# TouchPanel_ver__5.net
KiCad netlist of a schematic drawn in EAGLE
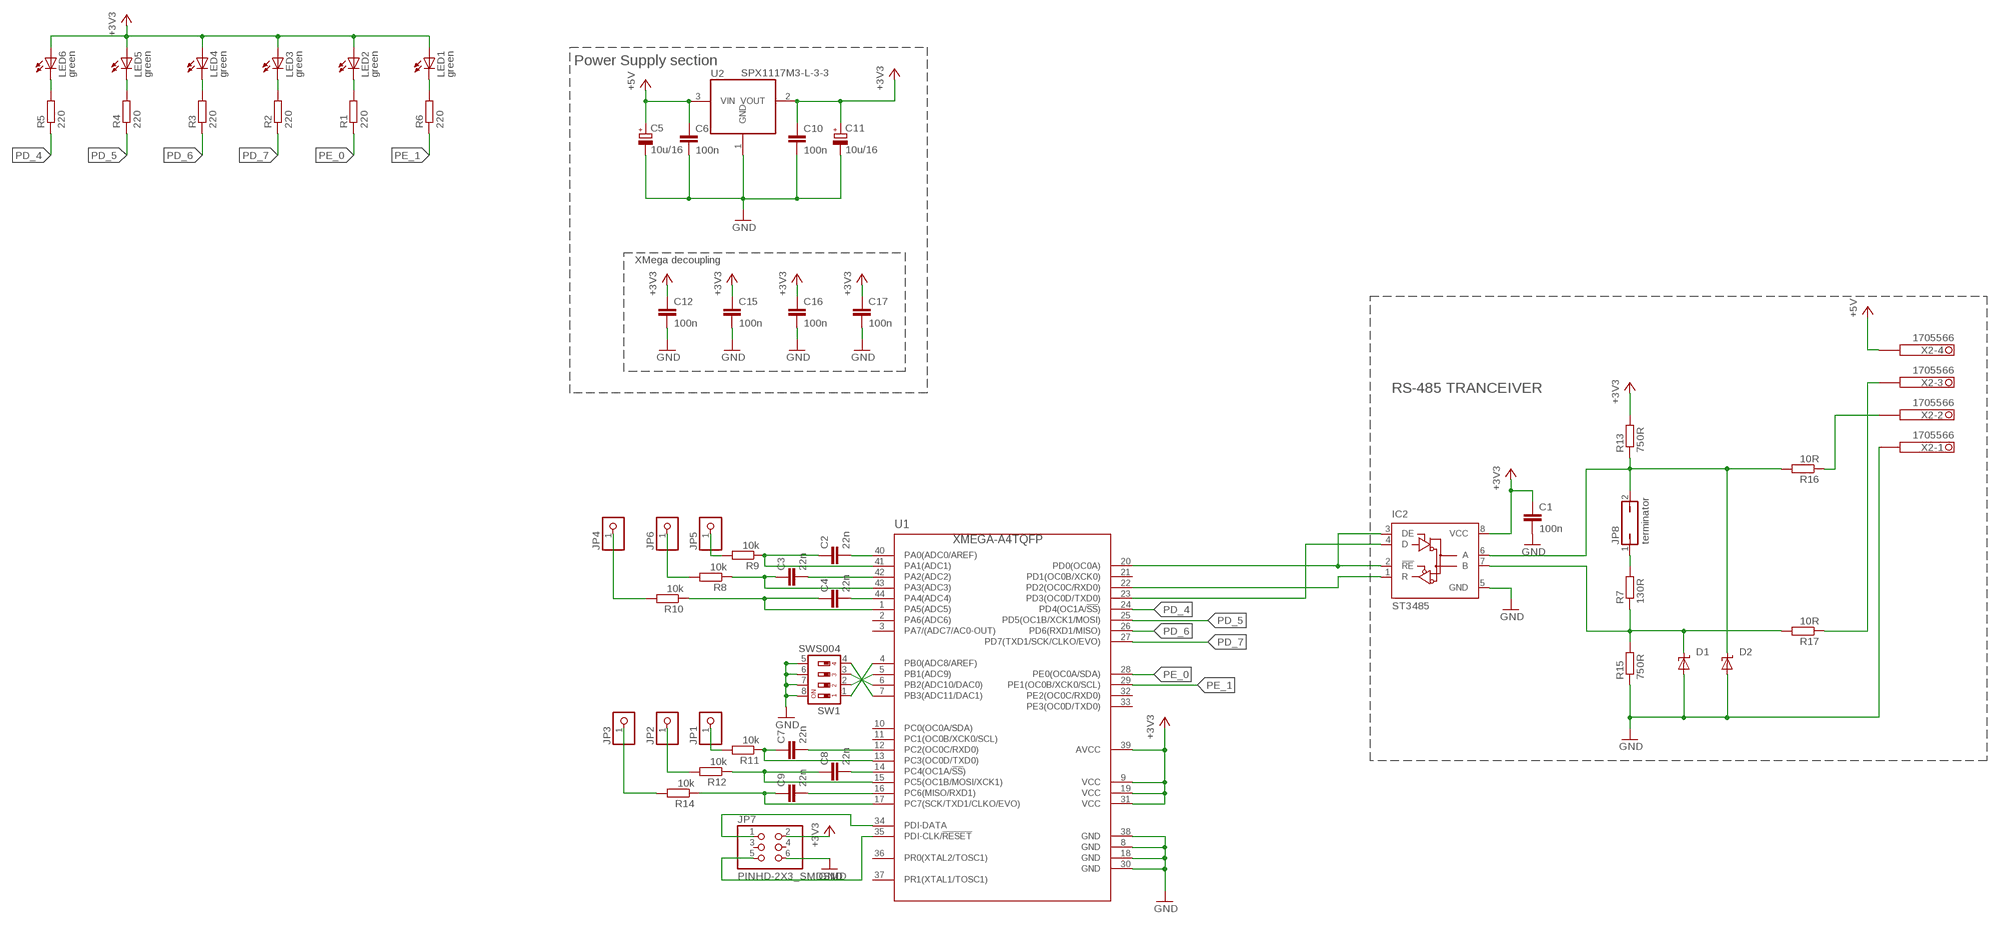
[diagram p0: schematic, sheet 1]

(export (version "E")
  (design (tool "Eeschema 10.0.6"))
  (components
    (comp (ref "C1")
      (value "100n")
      (footprint "eagle-import:C1206")
      (libsource (lib "eagle-import") (part "C-EUC1206"))
    )
    (comp (ref "C2")
      (value "22n")
      (footprint "eagle-import:C1206")
      (libsource (lib "eagle-import") (part "C-EUC1206"))
    )
    (comp (ref "C3")
      (value "22n")
      (footprint "eagle-import:C1206")
      (libsource (lib "eagle-import") (part "C-EUC1206"))
    )
    (comp (ref "C4")
      (value "22n")
      (footprint "eagle-import:C1206")
      (libsource (lib "eagle-import") (part "C-EUC1206"))
    )
    (comp (ref "C5")
      (value "10u/16")
      (footprint "eagle-import:SMC_B")
      (libsource (lib "eagle-import") (part "CPOL-EUSMCB"))
    )
    (comp (ref "C6")
      (value "100n")
      (footprint "eagle-import:C1206")
      (libsource (lib "eagle-import") (part "C-EUC1206"))
    )
    (comp (ref "C7")
      (value "22n")
      (footprint "eagle-import:C1206")
      (libsource (lib "eagle-import") (part "C-EUC1206"))
    )
    (comp (ref "C8")
      (value "22n")
      (footprint "eagle-import:C1206")
      (libsource (lib "eagle-import") (part "C-EUC1206"))
    )
    (comp (ref "C9")
      (value "22n")
      (footprint "eagle-import:C1206")
      (libsource (lib "eagle-import") (part "C-EUC1206"))
    )
    (comp (ref "C10")
      (value "100n")
      (footprint "eagle-import:C1206")
      (libsource (lib "eagle-import") (part "C-EUC1206"))
    )
    (comp (ref "C11")
      (value "10u/16")
      (footprint "eagle-import:SMC_B")
      (libsource (lib "eagle-import") (part "CPOL-EUSMCB"))
    )
    (comp (ref "C12")
      (value "100n")
      (footprint "eagle-import:C1206")
      (libsource (lib "eagle-import") (part "C-EUC1206"))
    )
    (comp (ref "C15")
      (value "100n")
      (footprint "eagle-import:C1206")
      (libsource (lib "eagle-import") (part "C-EUC1206"))
    )
    (comp (ref "C16")
      (value "100n")
      (footprint "eagle-import:C1206")
      (libsource (lib "eagle-import") (part "C-EUC1206"))
    )
    (comp (ref "C17")
      (value "100n")
      (footprint "eagle-import:C1206")
      (libsource (lib "eagle-import") (part "C-EUC1206"))
    )
    (comp (ref "D1")
      (value "SUPPRESSOR-SMBJ")
      (footprint "eagle-import:SMBJ")
      (libsource (lib "eagle-import") (part "SUPPRESSOR-SMBJ"))
    )
    (comp (ref "D2")
      (value "SUPPRESSOR-SMBJ")
      (footprint "eagle-import:SMBJ")
      (libsource (lib "eagle-import") (part "SUPPRESSOR-SMBJ"))
    )
    (comp (ref "IC2")
      (value "ST3485")
      (footprint "eagle-import:D_R-PDSO-G8")
      (libsource (lib "eagle-import") (part "75176AD"))
    )
    (comp (ref "JP1")
      (value "PINHD-1X1")
      (footprint "eagle-import:1X01")
      (libsource (lib "eagle-import") (part "PINHD-1X1"))
    )
    (comp (ref "JP2")
      (value "PINHD-1X1")
      (footprint "eagle-import:1X01")
      (libsource (lib "eagle-import") (part "PINHD-1X1"))
    )
    (comp (ref "JP3")
      (value "PINHD-1X1")
      (footprint "eagle-import:1X01")
      (libsource (lib "eagle-import") (part "PINHD-1X1"))
    )
    (comp (ref "JP4")
      (value "PINHD-1X1")
      (footprint "eagle-import:1X01")
      (libsource (lib "eagle-import") (part "PINHD-1X1"))
    )
    (comp (ref "JP5")
      (value "PINHD-1X1")
      (footprint "eagle-import:1X01")
      (libsource (lib "eagle-import") (part "PINHD-1X1"))
    )
    (comp (ref "JP6")
      (value "PINHD-1X1")
      (footprint "eagle-import:1X01")
      (libsource (lib "eagle-import") (part "PINHD-1X1"))
    )
    (comp (ref "JP7")
      (value "PINHD-2X3_SMDSMD")
      (footprint "eagle-import:2X03_SMD")
      (libsource (lib "eagle-import") (part "PINHD-2X3_SMDSMD"))
    )
    (comp (ref "JP8")
      (value "terminator")
      (footprint "eagle-import:JP1")
      (libsource (lib "eagle-import") (part "JP1Q"))
    )
    (comp (ref "LED1")
      (value "green")
      (footprint "eagle-import:MINI-TOPLED-SANTANA")
      (libsource (lib "eagle-import") (part "LEDTOPLED-SANTANA"))
    )
    (comp (ref "LED2")
      (value "green")
      (footprint "eagle-import:MINI-TOPLED-SANTANA")
      (libsource (lib "eagle-import") (part "LEDTOPLED-SANTANA"))
    )
    (comp (ref "LED3")
      (value "green")
      (footprint "eagle-import:MINI-TOPLED-SANTANA")
      (libsource (lib "eagle-import") (part "LEDTOPLED-SANTANA"))
    )
    (comp (ref "LED4")
      (value "green")
      (footprint "eagle-import:MINI-TOPLED-SANTANA")
      (libsource (lib "eagle-import") (part "LEDTOPLED-SANTANA"))
    )
    (comp (ref "LED5")
      (value "green")
      (footprint "eagle-import:MINI-TOPLED-SANTANA")
      (libsource (lib "eagle-import") (part "LEDTOPLED-SANTANA"))
    )
    (comp (ref "LED6")
      (value "green")
      (footprint "eagle-import:MINI-TOPLED-SANTANA")
      (libsource (lib "eagle-import") (part "LEDTOPLED-SANTANA"))
    )
    (comp (ref "R1")
      (value "220")
      (footprint "eagle-import:M1206")
      (libsource (lib "eagle-import") (part "R-EU_M1206"))
    )
    (comp (ref "R2")
      (value "220")
      (footprint "eagle-import:M1206")
      (libsource (lib "eagle-import") (part "R-EU_M1206"))
    )
    (comp (ref "R3")
      (value "220")
      (footprint "eagle-import:R1206")
      (libsource (lib "eagle-import") (part "R-EU_R1206"))
    )
    (comp (ref "R4")
      (value "220")
      (footprint "eagle-import:R1206")
      (libsource (lib "eagle-import") (part "R-EU_R1206"))
    )
    (comp (ref "R5")
      (value "220")
      (footprint "eagle-import:R1206")
      (libsource (lib "eagle-import") (part "R-EU_R1206"))
    )
    (comp (ref "R6")
      (value "220")
      (footprint "eagle-import:M1206")
      (libsource (lib "eagle-import") (part "R-EU_M1206"))
    )
    (comp (ref "R7")
      (value "130R")
      (footprint "eagle-import:M1206")
      (libsource (lib "eagle-import") (part "R-EU_M1206"))
    )
    (comp (ref "R8")
      (value "10k")
      (footprint "eagle-import:R1206")
      (libsource (lib "eagle-import") (part "R-EU_R1206"))
    )
    (comp (ref "R9")
      (value "10k")
      (footprint "eagle-import:R1206")
      (libsource (lib "eagle-import") (part "R-EU_R1206"))
    )
    (comp (ref "R10")
      (value "10k")
      (footprint "eagle-import:R1206")
      (libsource (lib "eagle-import") (part "R-EU_R1206"))
    )
    (comp (ref "R11")
      (value "10k")
      (footprint "eagle-import:R1206")
      (libsource (lib "eagle-import") (part "R-EU_R1206"))
    )
    (comp (ref "R12")
      (value "10k")
      (footprint "eagle-import:R1206")
      (libsource (lib "eagle-import") (part "R-EU_R1206"))
    )
    (comp (ref "R13")
      (value "750R")
      (footprint "eagle-import:M1206")
      (libsource (lib "eagle-import") (part "R-EU_M1206"))
    )
    (comp (ref "R14")
      (value "10k")
      (footprint "eagle-import:R1206")
      (libsource (lib "eagle-import") (part "R-EU_R1206"))
    )
    (comp (ref "R15")
      (value "750R")
      (footprint "eagle-import:M1206")
      (libsource (lib "eagle-import") (part "R-EU_M1206"))
    )
    (comp (ref "R16")
      (value "10R")
      (footprint "eagle-import:M1206")
      (libsource (lib "eagle-import") (part "R-EU_M1206"))
    )
    (comp (ref "R17")
      (value "10R")
      (footprint "eagle-import:M1206")
      (libsource (lib "eagle-import") (part "R-EU_M1206"))
    )
    (comp (ref "SW1")
      (value "SWS004")
      (footprint "eagle-import:SMS-004")
      (libsource (lib "eagle-import") (part "SWS004"))
    )
    (comp (ref "U1")
      (value "XMEGA-A4TQFP")
      (footprint "eagle-import:TQFP44")
      (libsource (lib "eagle-import") (part "XMEGA-A4TQFP"))
    )
    (comp (ref "U2")
      (value "SPX1117M3-L-3-3")
      (footprint "eagle-import:SOT223")
      (fields (field (name "MPN") "REG1117"))
      (libsource (lib "eagle-import") (part "REG1117"))
    )
    (comp (ref "X2")
      (value "1705566")
      (footprint "eagle-import:1705566")
      (libsource (lib "eagle-import") (part "1705566"))
    )
  )
  (nets
    (net (code "1") (name "+3V3") (class "Default")
      (node (ref "C1") (pin "1") (pinfunction "1_1") (pintype "passive"))
      (node (ref "C10") (pin "1") (pinfunction "1_1") (pintype "passive"))
      (node (ref "C11") (pin "+") (pinfunction "+_+") (pintype "passive"))
      (node (ref "C12") (pin "1") (pinfunction "1_1") (pintype "passive"))
      (node (ref "C15") (pin "1") (pinfunction "1_1") (pintype "passive"))
      (node (ref "C16") (pin "1") (pinfunction "1_1") (pintype "passive"))
      (node (ref "C17") (pin "1") (pinfunction "1_1") (pintype "passive"))
      (node (ref "IC2") (pin "8") (pinfunction "VCC_8") (pintype "power_in"))
      (node (ref "JP7") (pin "2") (pinfunction "2_2") (pintype "passive"))
      (node (ref "LED1") (pin "A") (pinfunction "A_A") (pintype "passive"))
      (node (ref "LED2") (pin "A") (pinfunction "A_A") (pintype "passive"))
      (node (ref "LED3") (pin "A") (pinfunction "A_A") (pintype "passive"))
      (node (ref "LED4") (pin "A") (pinfunction "A_A") (pintype "passive"))
      (node (ref "LED5") (pin "A") (pinfunction "A_A") (pintype "passive"))
      (node (ref "LED6") (pin "A") (pinfunction "A_A") (pintype "passive"))
      (node (ref "R13") (pin "2") (pinfunction "2_2") (pintype "passive"))
      (node (ref "U1") (pin "19") (pinfunction "VCC_19") (pintype "power_in"))
      (node (ref "U1") (pin "31") (pinfunction "VCC_31") (pintype "power_in"))
      (node (ref "U1") (pin "39") (pinfunction "AVCC_39") (pintype "power_in"))
      (node (ref "U1") (pin "9") (pinfunction "VCC_9") (pintype "power_in"))
      (node (ref "U2") (pin "2") (pinfunction "VOUT_2") (pintype "output"))
    )
    (net (code "2") (name "+5V") (class "Default")
      (node (ref "C5") (pin "+") (pinfunction "+_+") (pintype "passive"))
      (node (ref "C6") (pin "1") (pinfunction "1_1") (pintype "passive"))
      (node (ref "U2") (pin "3") (pinfunction "VIN_3") (pintype "input"))
      (node (ref "X2") (pin "4.2") (pinfunction "1B_4.2") (pintype "passive"))
    )
    (net (code "3") (name "GND") (class "Default")
      (node (ref "C1") (pin "2") (pinfunction "2_2") (pintype "passive"))
      (node (ref "C10") (pin "2") (pinfunction "2_2") (pintype "passive"))
      (node (ref "C11") (pin "-") (pinfunction "-_-") (pintype "passive"))
      (node (ref "C12") (pin "2") (pinfunction "2_2") (pintype "passive"))
      (node (ref "C15") (pin "2") (pinfunction "2_2") (pintype "passive"))
      (node (ref "C16") (pin "2") (pinfunction "2_2") (pintype "passive"))
      (node (ref "C17") (pin "2") (pinfunction "2_2") (pintype "passive"))
      (node (ref "C5") (pin "-") (pinfunction "-_-") (pintype "passive"))
      (node (ref "C6") (pin "2") (pinfunction "2_2") (pintype "passive"))
      (node (ref "D1") (pin "A") (pinfunction "A_A") (pintype "passive"))
      (node (ref "D2") (pin "A") (pinfunction "A_A") (pintype "passive"))
      (node (ref "IC2") (pin "5") (pinfunction "GND_5") (pintype "power_in"))
      (node (ref "JP7") (pin "6") (pinfunction "6_6") (pintype "passive"))
      (node (ref "R15") (pin "1") (pinfunction "1_1") (pintype "passive"))
      (node (ref "SW1") (pin "5") (pinfunction "5_5") (pintype "passive"))
      (node (ref "SW1") (pin "6") (pinfunction "6_6") (pintype "passive"))
      (node (ref "SW1") (pin "7") (pinfunction "7_7") (pintype "passive"))
      (node (ref "SW1") (pin "8") (pinfunction "8_8") (pintype "passive"))
      (node (ref "U1") (pin "18") (pinfunction "GND_18") (pintype "power_in"))
      (node (ref "U1") (pin "30") (pinfunction "GND_30") (pintype "power_in"))
      (node (ref "U1") (pin "38") (pinfunction "GND_38") (pintype "power_in"))
      (node (ref "U1") (pin "8") (pinfunction "GND_8") (pintype "power_in"))
      (node (ref "U2") (pin "1") (pinfunction "GND_1") (pintype "power_in"))
      (node (ref "X2") (pin "1.2") (pinfunction "1B_1.2") (pintype "passive"))
    )
    (net (code "4") (name "Net-(IC2-A)") (class "Default")
      (node (ref "D2") (pin "C") (pinfunction "C_C") (pintype "passive"))
      (node (ref "IC2") (pin "6") (pinfunction "A_6") (pintype "output"))
      (node (ref "JP8") (pin "2") (pinfunction "2_2") (pintype "passive"))
      (node (ref "R13") (pin "1") (pinfunction "1_1") (pintype "passive"))
      (node (ref "R16") (pin "2") (pinfunction "2_2") (pintype "passive"))
    )
    (net (code "5") (name "Net-(IC2-B)") (class "Default")
      (node (ref "D1") (pin "C") (pinfunction "C_C") (pintype "passive"))
      (node (ref "IC2") (pin "7") (pinfunction "B_7") (pintype "output"))
      (node (ref "R15") (pin "2") (pinfunction "2_2") (pintype "passive"))
      (node (ref "R17") (pin "2") (pinfunction "2_2") (pintype "passive"))
      (node (ref "R7") (pin "1") (pinfunction "1_1") (pintype "passive"))
    )
    (net (code "6") (name "Net-(IC2-D)") (class "Default")
      (node (ref "IC2") (pin "4") (pinfunction "D_4") (pintype "input"))
      (node (ref "U1") (pin "23") (pinfunction "PD3(OC0D/TXD0)_23") (pintype "bidirectional"))
    )
    (net (code "7") (name "Net-(IC2-DE)") (class "Default")
      (node (ref "IC2") (pin "2") (pinfunction "~{RE}_2") (pintype "input"))
      (node (ref "IC2") (pin "3") (pinfunction "DE_3") (pintype "input"))
      (node (ref "U1") (pin "20") (pinfunction "PD0(OC0A)_20") (pintype "bidirectional"))
    )
    (net (code "8") (name "Net-(IC2-R)") (class "Default")
      (node (ref "IC2") (pin "1") (pinfunction "R_1") (pintype "input"))
      (node (ref "U1") (pin "22") (pinfunction "PD2(OC0C/RXD0)_22") (pintype "bidirectional"))
    )
    (net (code "9") (name "Net-(JP1-Pad1)") (class "Default")
      (node (ref "JP1") (pin "1") (pinfunction "1_1") (pintype "passive"))
      (node (ref "R11") (pin "2") (pinfunction "2_2") (pintype "passive"))
    )
    (net (code "10") (name "Net-(JP2-Pad1)") (class "Default")
      (node (ref "JP2") (pin "1") (pinfunction "1_1") (pintype "passive"))
      (node (ref "R12") (pin "2") (pinfunction "2_2") (pintype "passive"))
    )
    (net (code "11") (name "Net-(JP3-Pad1)") (class "Default")
      (node (ref "JP3") (pin "1") (pinfunction "1_1") (pintype "passive"))
      (node (ref "R14") (pin "2") (pinfunction "2_2") (pintype "passive"))
    )
    (net (code "12") (name "Net-(JP4-Pad1)") (class "Default")
      (node (ref "JP4") (pin "1") (pinfunction "1_1") (pintype "passive"))
      (node (ref "R10") (pin "2") (pinfunction "2_2") (pintype "passive"))
    )
    (net (code "13") (name "Net-(JP5-Pad1)") (class "Default")
      (node (ref "JP5") (pin "1") (pinfunction "1_1") (pintype "passive"))
      (node (ref "R9") (pin "2") (pinfunction "2_2") (pintype "passive"))
    )
    (net (code "14") (name "Net-(JP6-Pad1)") (class "Default")
      (node (ref "JP6") (pin "1") (pinfunction "1_1") (pintype "passive"))
      (node (ref "R8") (pin "2") (pinfunction "2_2") (pintype "passive"))
    )
    (net (code "15") (name "Net-(JP8-Pad1)") (class "Default")
      (node (ref "JP8") (pin "1") (pinfunction "1_1") (pintype "passive"))
      (node (ref "R7") (pin "2") (pinfunction "2_2") (pintype "passive"))
    )
    (net (code "16") (name "Net-(LED1-PadC)") (class "Default")
      (node (ref "LED1") (pin "C") (pinfunction "C_C") (pintype "passive"))
      (node (ref "R6") (pin "2") (pinfunction "2_2") (pintype "passive"))
    )
    (net (code "17") (name "Net-(LED2-PadC)") (class "Default")
      (node (ref "LED2") (pin "C") (pinfunction "C_C") (pintype "passive"))
      (node (ref "R1") (pin "2") (pinfunction "2_2") (pintype "passive"))
    )
    (net (code "18") (name "Net-(LED3-PadC)") (class "Default")
      (node (ref "LED3") (pin "C") (pinfunction "C_C") (pintype "passive"))
      (node (ref "R2") (pin "2") (pinfunction "2_2") (pintype "passive"))
    )
    (net (code "19") (name "Net-(LED4-PadC)") (class "Default")
      (node (ref "LED4") (pin "C") (pinfunction "C_C") (pintype "passive"))
      (node (ref "R3") (pin "2") (pinfunction "2_2") (pintype "passive"))
    )
    (net (code "20") (name "Net-(LED5-PadC)") (class "Default")
      (node (ref "LED5") (pin "C") (pinfunction "C_C") (pintype "passive"))
      (node (ref "R4") (pin "2") (pinfunction "2_2") (pintype "passive"))
    )
    (net (code "21") (name "Net-(LED6-PadC)") (class "Default")
      (node (ref "LED6") (pin "C") (pinfunction "C_C") (pintype "passive"))
      (node (ref "R5") (pin "2") (pinfunction "2_2") (pintype "passive"))
    )
    (net (code "22") (name "Net-(U1-PA0(ADC0{slash}AREF))") (class "Default")
      (node (ref "C2") (pin "2") (pinfunction "2_2") (pintype "passive"))
      (node (ref "U1") (pin "40") (pinfunction "PA0(ADC0/AREF)_40") (pintype "bidirectional"))
    )
    (net (code "23") (name "Net-(U1-PA1(ADC1))") (class "Default")
      (node (ref "C2") (pin "1") (pinfunction "1_1") (pintype "passive"))
      (node (ref "R9") (pin "1") (pinfunction "1_1") (pintype "passive"))
      (node (ref "U1") (pin "41") (pinfunction "PA1(ADC1)_41") (pintype "bidirectional"))
    )
    (net (code "24") (name "Net-(U1-PA2(ADC2))") (class "Default")
      (node (ref "C3") (pin "2") (pinfunction "2_2") (pintype "passive"))
      (node (ref "U1") (pin "42") (pinfunction "PA2(ADC2)_42") (pintype "bidirectional"))
    )
    (net (code "25") (name "Net-(U1-PA3(ADC3))") (class "Default")
      (node (ref "C3") (pin "1") (pinfunction "1_1") (pintype "passive"))
      (node (ref "R8") (pin "1") (pinfunction "1_1") (pintype "passive"))
      (node (ref "U1") (pin "43") (pinfunction "PA3(ADC3)_43") (pintype "bidirectional"))
    )
    (net (code "26") (name "Net-(U1-PA4(ADC4))") (class "Default")
      (node (ref "C4") (pin "2") (pinfunction "2_2") (pintype "passive"))
      (node (ref "U1") (pin "44") (pinfunction "PA4(ADC4)_44") (pintype "bidirectional"))
    )
    (net (code "27") (name "Net-(U1-PA5(ADC5))") (class "Default")
      (node (ref "C4") (pin "1") (pinfunction "1_1") (pintype "passive"))
      (node (ref "R10") (pin "1") (pinfunction "1_1") (pintype "passive"))
      (node (ref "U1") (pin "1") (pinfunction "PA5(ADC5)_1") (pintype "bidirectional"))
    )
    (net (code "28") (name "Net-(U1-PB0(ADC8{slash}AREF))") (class "Default")
      (node (ref "SW1") (pin "1") (pinfunction "1_1") (pintype "passive"))
      (node (ref "U1") (pin "4") (pinfunction "PB0(ADC8/AREF)_4") (pintype "bidirectional"))
    )
    (net (code "29") (name "Net-(U1-PB1(ADC9))") (class "Default")
      (node (ref "SW1") (pin "2") (pinfunction "2_2") (pintype "passive"))
      (node (ref "U1") (pin "5") (pinfunction "PB1(ADC9)_5") (pintype "bidirectional"))
    )
    (net (code "30") (name "Net-(U1-PB2(ADC10{slash}DAC0))") (class "Default")
      (node (ref "SW1") (pin "3") (pinfunction "3_3") (pintype "passive"))
      (node (ref "U1") (pin "6") (pinfunction "PB2(ADC10/DAC0)_6") (pintype "bidirectional"))
    )
    (net (code "31") (name "Net-(U1-PB3(ADC11{slash}DAC1))") (class "Default")
      (node (ref "SW1") (pin "4") (pinfunction "4_4") (pintype "passive"))
      (node (ref "U1") (pin "7") (pinfunction "PB3(ADC11/DAC1)_7") (pintype "bidirectional"))
    )
    (net (code "32") (name "Net-(U1-PC2(OC0C{slash}RXD0))") (class "Default")
      (node (ref "C7") (pin "2") (pinfunction "2_2") (pintype "passive"))
      (node (ref "U1") (pin "12") (pinfunction "PC2(OC0C/RXD0)_12") (pintype "bidirectional"))
    )
    (net (code "33") (name "Net-(U1-PC3(OC0D{slash}TXD0))") (class "Default")
      (node (ref "C7") (pin "1") (pinfunction "1_1") (pintype "passive"))
      (node (ref "R11") (pin "1") (pinfunction "1_1") (pintype "passive"))
      (node (ref "U1") (pin "13") (pinfunction "PC3(OC0D/TXD0)_13") (pintype "bidirectional"))
    )
    (net (code "34") (name "Net-(U1-PC4(OC1A{slash}~{SS}))") (class "Default")
      (node (ref "C8") (pin "2") (pinfunction "2_2") (pintype "passive"))
      (node (ref "U1") (pin "14") (pinfunction "PC4(OC1A/~{SS})_14") (pintype "bidirectional"))
    )
    (net (code "35") (name "Net-(U1-PC5(OC1B{slash}MOSI{slash}XCK1))") (class "Default")
      (node (ref "C8") (pin "1") (pinfunction "1_1") (pintype "passive"))
      (node (ref "R12") (pin "1") (pinfunction "1_1") (pintype "passive"))
      (node (ref "U1") (pin "15") (pinfunction "PC5(OC1B/MOSI/XCK1)_15") (pintype "bidirectional"))
    )
    (net (code "36") (name "Net-(U1-PC6(MISO{slash}RXD1))") (class "Default")
      (node (ref "C9") (pin "2") (pinfunction "2_2") (pintype "passive"))
      (node (ref "U1") (pin "16") (pinfunction "PC6(MISO/RXD1)_16") (pintype "bidirectional"))
    )
    (net (code "37") (name "Net-(U1-PC7(SCK{slash}TXD1{slash}CLKO{slash}EVO))") (class "Default")
      (node (ref "C9") (pin "1") (pinfunction "1_1") (pintype "passive"))
      (node (ref "R14") (pin "1") (pinfunction "1_1") (pintype "passive"))
      (node (ref "U1") (pin "17") (pinfunction "PC7(SCK/TXD1/CLKO/EVO)_17") (pintype "bidirectional"))
    )
    (net (code "38") (name "Net-(U1-PDI-CLK{slash}~{RESET})") (class "Default")
      (node (ref "JP7") (pin "5") (pinfunction "5_5") (pintype "passive"))
      (node (ref "U1") (pin "35") (pinfunction "PDI-CLK/~{RESET}_35") (pintype "input"))
    )
    (net (code "39") (name "Net-(U1-PDI-DATA)") (class "Default")
      (node (ref "JP7") (pin "1") (pinfunction "1_1") (pintype "passive"))
      (node (ref "U1") (pin "34") (pinfunction "PDI-DATA_34") (pintype "bidirectional"))
    )
    (net (code "40") (name "Net-(X2B-1B)") (class "Default")
      (node (ref "R16") (pin "1") (pinfunction "1_1") (pintype "passive"))
      (node (ref "X2") (pin "2.2") (pinfunction "1B_2.2") (pintype "passive"))
    )
    (net (code "41") (name "Net-(X2C-1B)") (class "Default")
      (node (ref "R17") (pin "1") (pinfunction "1_1") (pintype "passive"))
      (node (ref "X2") (pin "3.2") (pinfunction "1B_3.2") (pintype "passive"))
    )
    (net (code "42") (name "PD_4") (class "Default")
      (node (ref "R5") (pin "1") (pinfunction "1_1") (pintype "passive"))
      (node (ref "U1") (pin "24") (pinfunction "PD4(OC1A/~{SS})_24") (pintype "bidirectional"))
    )
    (net (code "43") (name "PD_5") (class "Default")
      (node (ref "R4") (pin "1") (pinfunction "1_1") (pintype "passive"))
      (node (ref "U1") (pin "25") (pinfunction "PD5(OC1B/XCK1/MOSI)_25") (pintype "bidirectional"))
    )
    (net (code "44") (name "PD_6") (class "Default")
      (node (ref "R3") (pin "1") (pinfunction "1_1") (pintype "passive"))
      (node (ref "U1") (pin "26") (pinfunction "PD6(RXD1/MISO)_26") (pintype "bidirectional"))
    )
    (net (code "45") (name "PD_7") (class "Default")
      (node (ref "R2") (pin "1") (pinfunction "1_1") (pintype "passive"))
      (node (ref "U1") (pin "27") (pinfunction "PD7(TXD1/SCK/CLKO/EVO)_27") (pintype "bidirectional"))
    )
    (net (code "46") (name "PE_0") (class "Default")
      (node (ref "R1") (pin "1") (pinfunction "1_1") (pintype "passive"))
      (node (ref "U1") (pin "28") (pinfunction "PE0(OC0A/SDA)_28") (pintype "bidirectional"))
    )
    (net (code "47") (name "PE_1") (class "Default")
      (node (ref "R6") (pin "1") (pinfunction "1_1") (pintype "passive"))
      (node (ref "U1") (pin "29") (pinfunction "PE1(OC0B/XCK0/SCL)_29") (pintype "bidirectional"))
    )
    (net (code "48") (name "unconnected-(JP7-Pad3)") (class "Default")
      (node (ref "JP7") (pin "3") (pinfunction "3_3") (pintype "passive"))
    )
    (net (code "49") (name "unconnected-(JP7-Pad4)") (class "Default")
      (node (ref "JP7") (pin "4") (pinfunction "4_4") (pintype "passive"))
    )
    (net (code "50") (name "unconnected-(U1-PA6(ADC6)-Pad2)") (class "Default")
      (node (ref "U1") (pin "2") (pinfunction "PA6(ADC6)_2") (pintype "bidirectional"))
    )
    (net (code "51") (name "unconnected-(U1-PA7{slash}(ADC7{slash}AC0-OUT)-Pad3)") (class "Default")
      (node (ref "U1") (pin "3") (pinfunction "PA7/(ADC7/AC0-OUT)_3") (pintype "bidirectional"))
    )
    (net (code "52") (name "unconnected-(U1-PC0(OC0A{slash}SDA)-Pad10)") (class "Default")
      (node (ref "U1") (pin "10") (pinfunction "PC0(OC0A/SDA)_10") (pintype "bidirectional"))
    )
    (net (code "53") (name "unconnected-(U1-PC1(OC0B{slash}XCK0{slash}SCL)-Pad11)") (class "Default")
      (node (ref "U1") (pin "11") (pinfunction "PC1(OC0B/XCK0/SCL)_11") (pintype "bidirectional"))
    )
    (net (code "54") (name "unconnected-(U1-PD1(OC0B{slash}XCK0)-Pad21)") (class "Default")
      (node (ref "U1") (pin "21") (pinfunction "PD1(OC0B/XCK0)_21") (pintype "bidirectional"))
    )
    (net (code "55") (name "unconnected-(U1-PE2(OC0C{slash}RXD0)-Pad32)") (class "Default")
      (node (ref "U1") (pin "32") (pinfunction "PE2(OC0C/RXD0)_32") (pintype "bidirectional"))
    )
    (net (code "56") (name "unconnected-(U1-PE3(OC0D{slash}TXD0)-Pad33)") (class "Default")
      (node (ref "U1") (pin "33") (pinfunction "PE3(OC0D/TXD0)_33") (pintype "bidirectional"))
    )
    (net (code "57") (name "unconnected-(U1-PR0(XTAL2{slash}TOSC1)-Pad36)") (class "Default")
      (node (ref "U1") (pin "36") (pinfunction "PR0(XTAL2/TOSC1)_36") (pintype "bidirectional"))
    )
    (net (code "58") (name "unconnected-(U1-PR1(XTAL1{slash}TOSC1)-Pad37)") (class "Default")
      (node (ref "U1") (pin "37") (pinfunction "PR1(XTAL1/TOSC1)_37") (pintype "bidirectional"))
    )
    (net (code "59") (name "unconnected-(X2A-1A-Pad1.1)") (class "Default")
      (node (ref "X2") (pin "1.1") (pinfunction "1A_1.1") (pintype "passive"))
    )
    (net (code "60") (name "unconnected-(X2B-1A-Pad2.1)") (class "Default")
      (node (ref "X2") (pin "2.1") (pinfunction "1A_2.1") (pintype "passive"))
    )
    (net (code "61") (name "unconnected-(X2C-1A-Pad3.1)") (class "Default")
      (node (ref "X2") (pin "3.1") (pinfunction "1A_3.1") (pintype "passive"))
    )
    (net (code "62") (name "unconnected-(X2D-1A-Pad4.1)") (class "Default")
      (node (ref "X2") (pin "4.1") (pinfunction "1A_4.1") (pintype "passive"))
    )
  )
)
